# EngineeringModelBoard_6-2015_Lee_Jenny_2.net
KiCad netlist of a schematic drawn in EAGLE
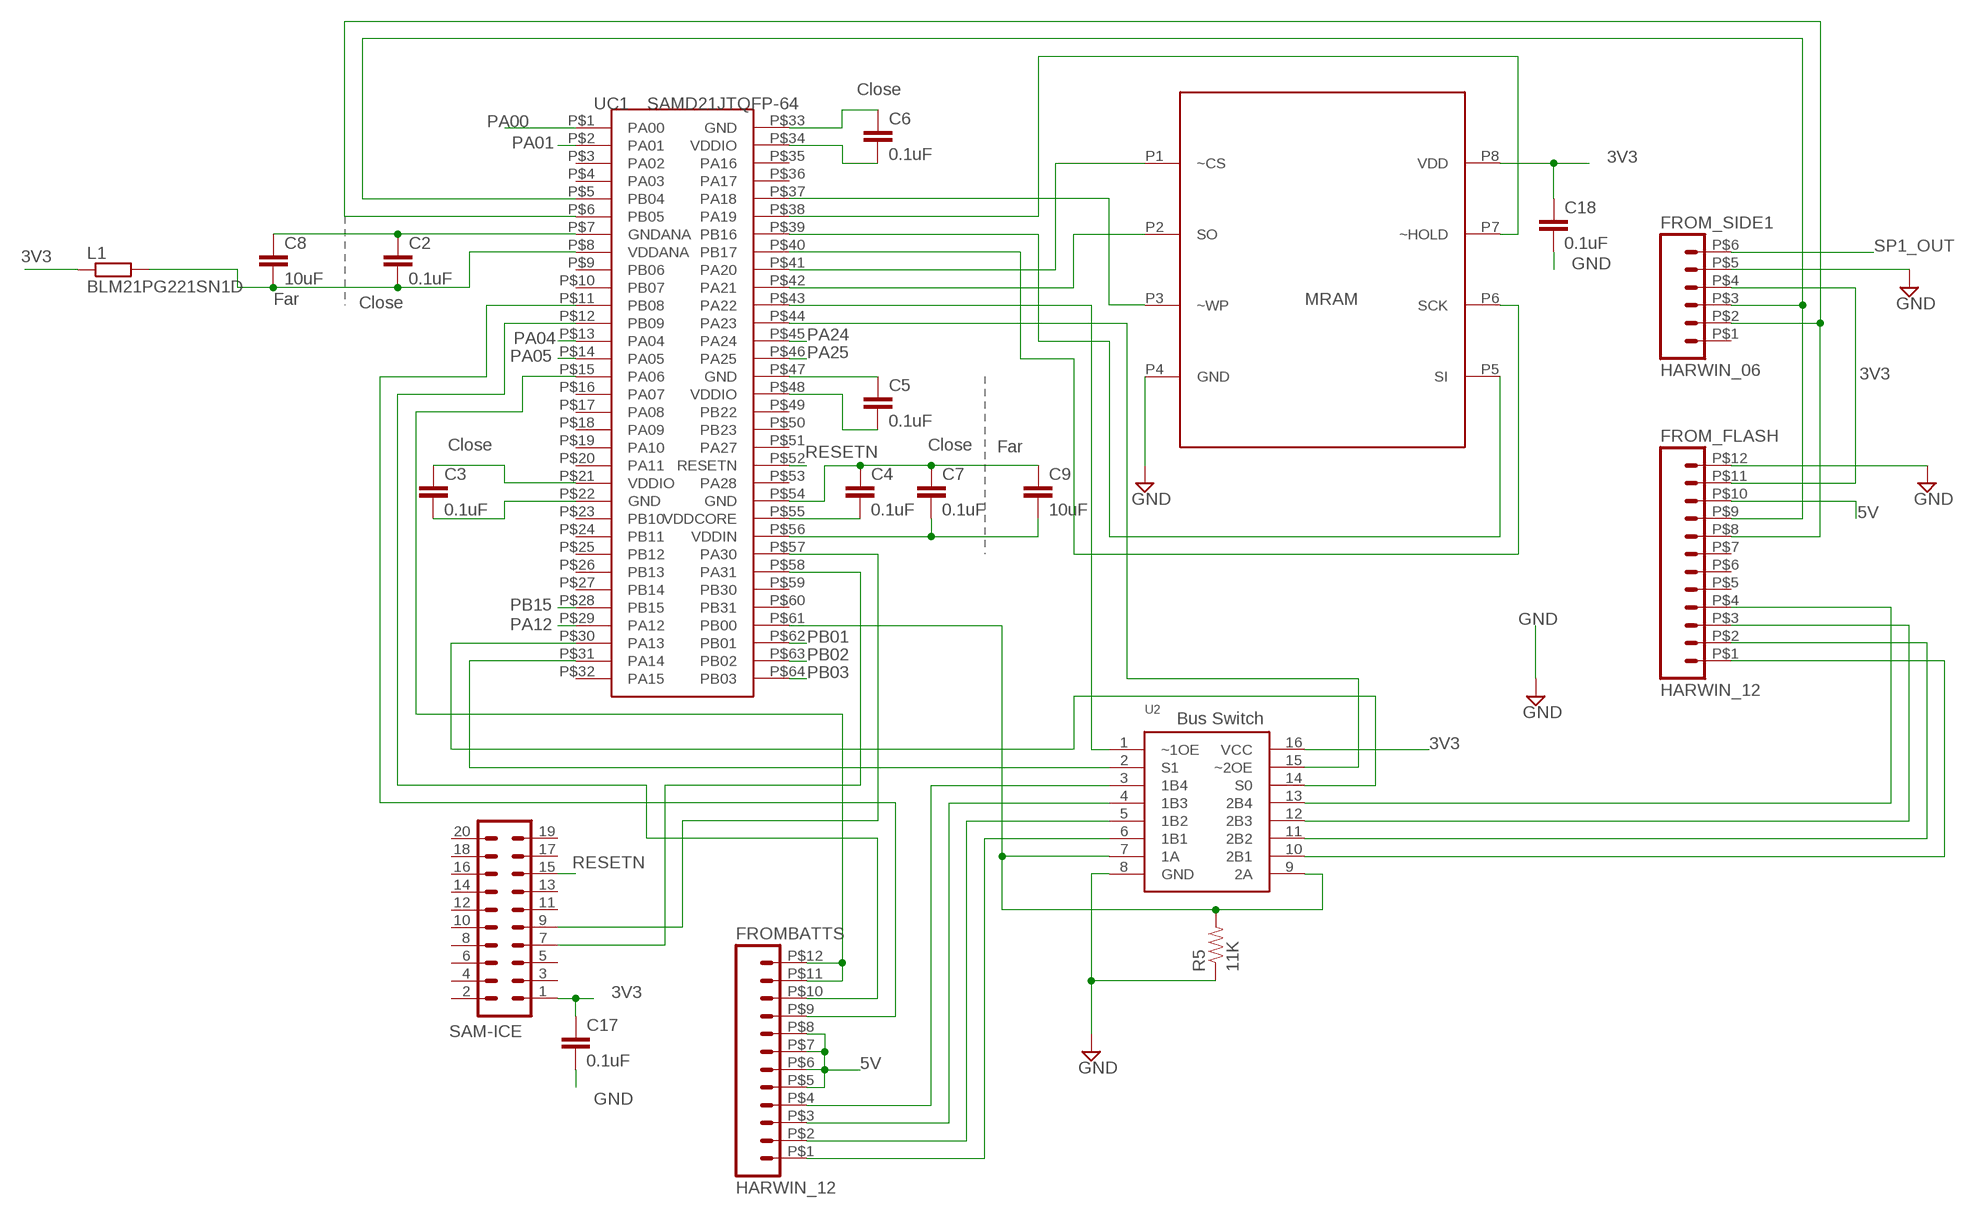
[diagram p0: schematic, sheet 1]
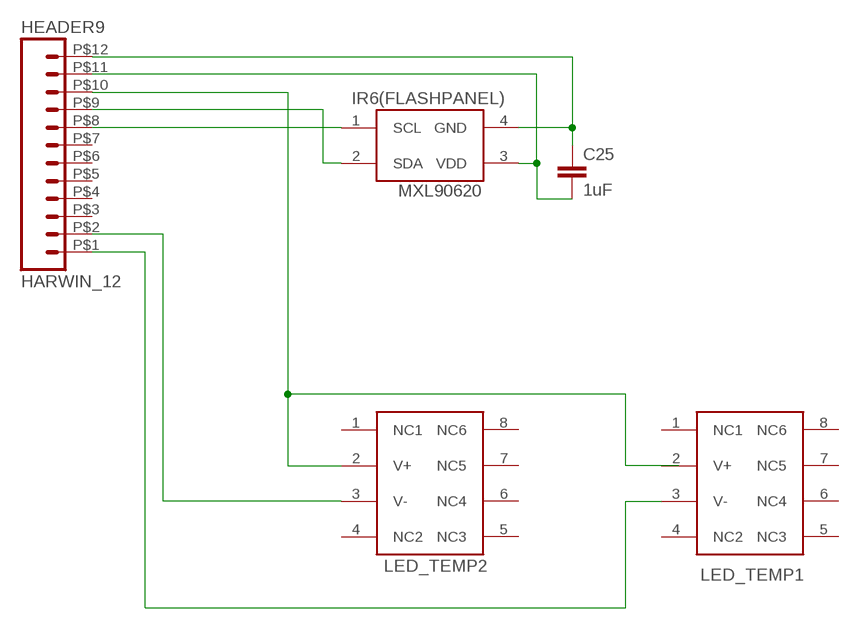
[diagram p1: schematic, sheet 2]
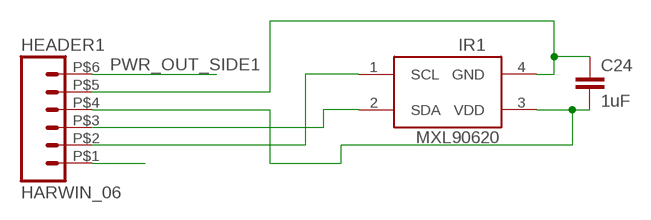
[diagram p2: schematic, sheet 3]
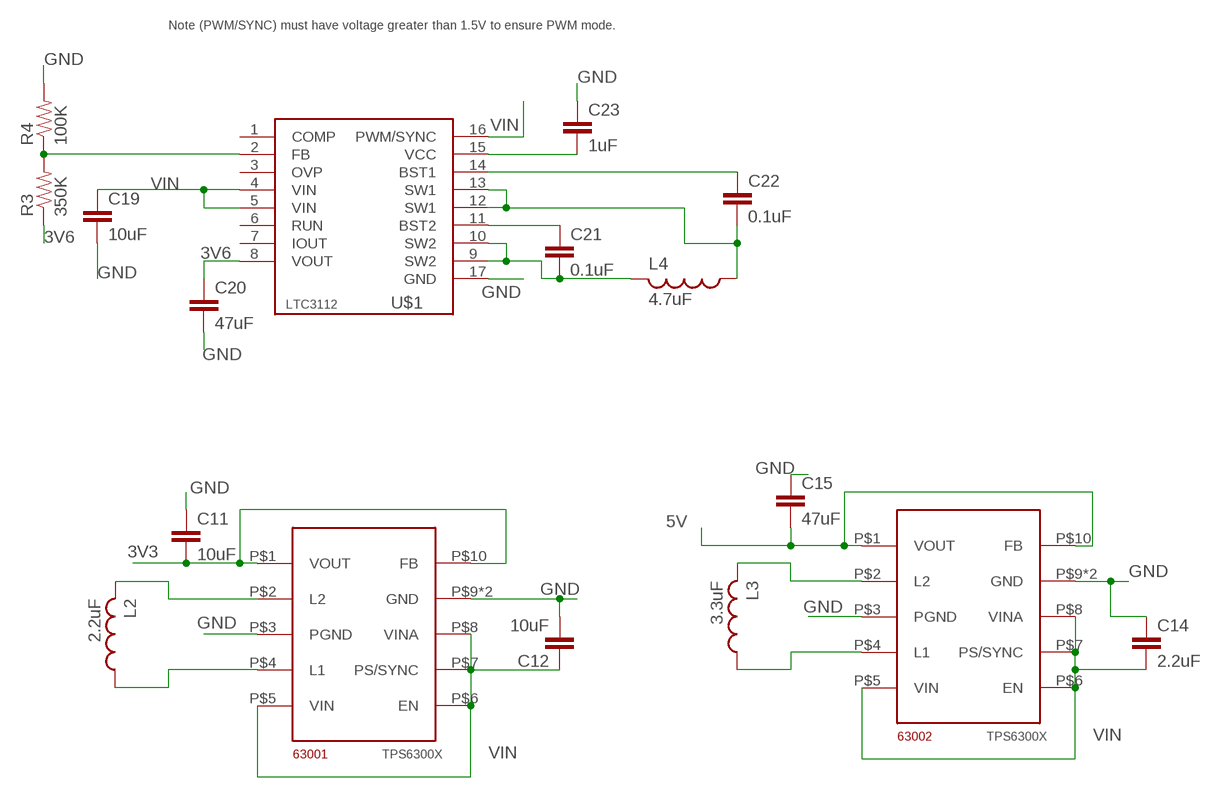
[diagram p3: schematic, sheet 4]
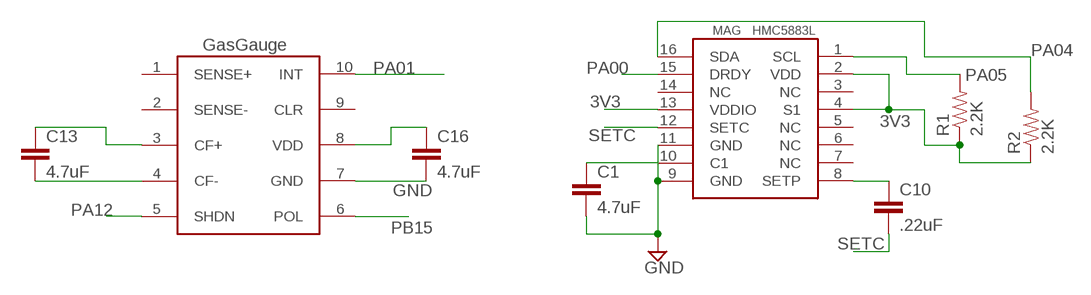
[diagram p4: schematic, sheet 5]
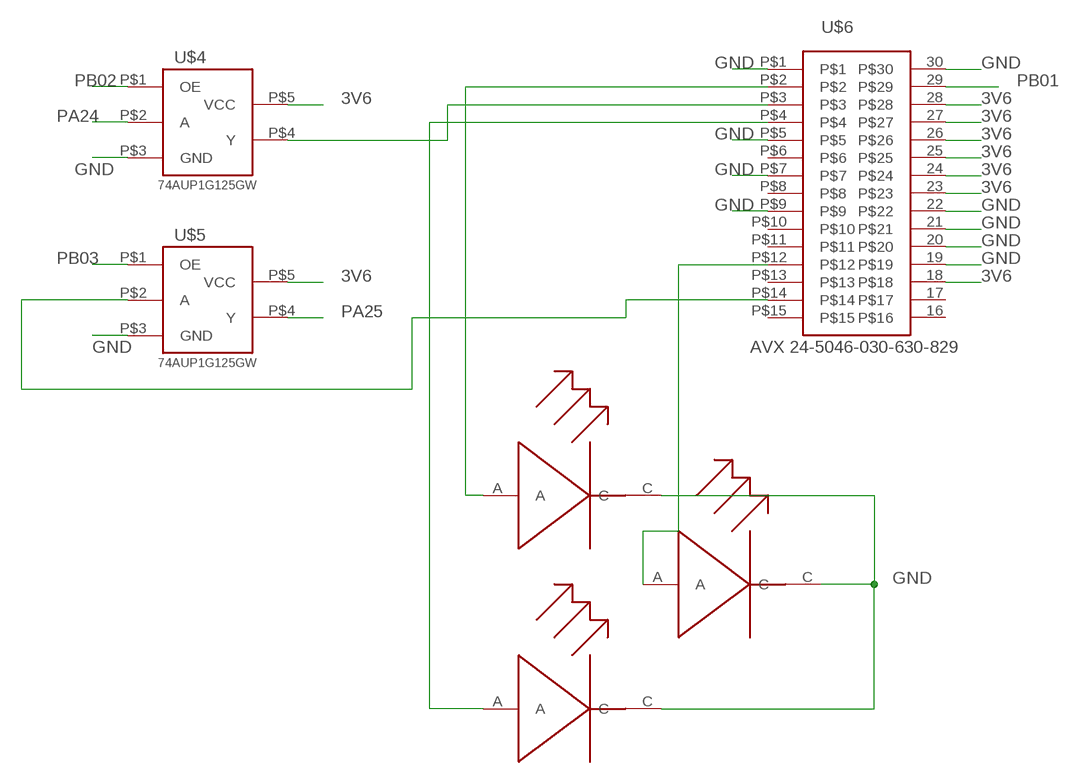
[diagram p5: schematic, sheet 6]
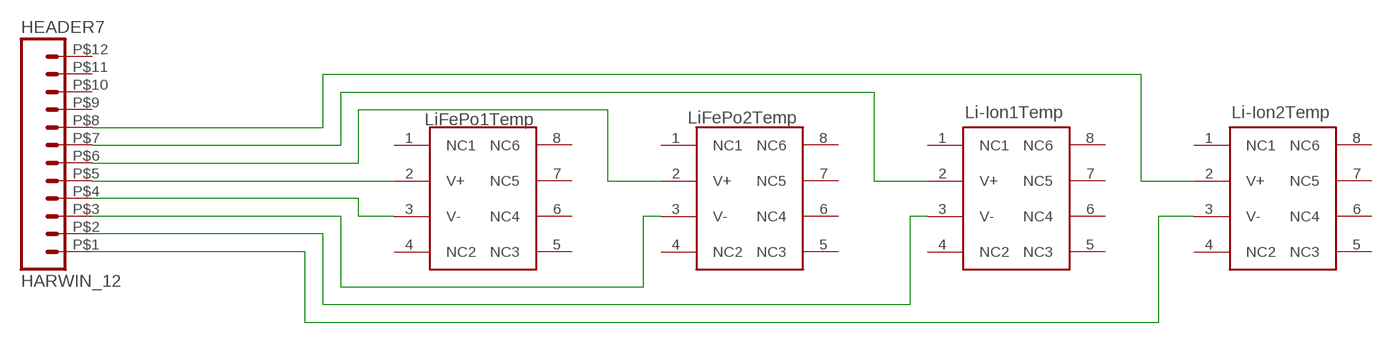
[diagram p6: schematic, sheet 7]

(export (version "E")
  (design (tool "Eeschema 10.0.6"))
  (components
    (comp (ref "C2")
      (value "0.1uF")
      (footprint "eagle-import:0805")
      (libsource (lib "eagle-import") (part "CAP0805"))
    )
    (comp (ref "C3")
      (value "0.1uF")
      (footprint "eagle-import:0805")
      (libsource (lib "eagle-import") (part "CAP0805"))
    )
    (comp (ref "C4")
      (value "0.1uF")
      (footprint "eagle-import:0805")
      (libsource (lib "eagle-import") (part "CAP0805"))
    )
    (comp (ref "C5")
      (value "0.1uF")
      (footprint "eagle-import:0805")
      (libsource (lib "eagle-import") (part "CAP0805"))
    )
    (comp (ref "C6")
      (value "0.1uF")
      (footprint "eagle-import:0805")
      (libsource (lib "eagle-import") (part "CAP0805"))
    )
    (comp (ref "C7")
      (value "0.1uF")
      (footprint "eagle-import:0805")
      (libsource (lib "eagle-import") (part "CAP0805"))
    )
    (comp (ref "C8")
      (value "10uF")
      (footprint "eagle-import:0805")
      (libsource (lib "eagle-import") (part "CAP0805"))
    )
    (comp (ref "C9")
      (value "10uF")
      (footprint "eagle-import:0805")
      (libsource (lib "eagle-import") (part "CAP0805"))
    )
    (comp (ref "C17")
      (value "0.1uF")
      (footprint "eagle-import:0805")
      (libsource (lib "eagle-import") (part "CAP0805"))
    )
    (comp (ref "C18")
      (value "0.1uF")
      (footprint "eagle-import:0805")
      (libsource (lib "eagle-import") (part "CAP0805"))
    )
    (comp (ref "FROMBATTS")
      (value "HARWIN_12")
      (footprint "eagle-import:HARWIN_DATAMATE_12")
      (libsource (lib "eagle-import") (part "HARWIN_12"))
    )
    (comp (ref "FROM_FLASH")
      (value "HARWIN_12")
      (footprint "eagle-import:HARWIN_DATAMATE_12")
      (libsource (lib "eagle-import") (part "HARWIN_12"))
    )
    (comp (ref "FROM_SIDE1")
      (value "HARWIN_06")
      (footprint "eagle-import:HARWIN_DATAMATE_6")
      (libsource (lib "eagle-import") (part "HARWIN_06"))
    )
    (comp (ref "L1")
      (value "BLM21PG221SN1D")
      (footprint "eagle-import:R0805")
      (libsource (lib "eagle-import") (part "R-EU_R0805"))
    )
    (comp (ref "R5")
      (value "11K")
      (footprint "eagle-import:0805")
      (libsource (lib "eagle-import") (part "RESISTOR"))
    )
    (comp (ref "SAM-ICE")
      (value "IDC_JTAG_CONNECTOR")
      (footprint "eagle-import:2X10")
      (libsource (lib "eagle-import") (part "IDC_JTAG_CONNECTOR"))
    )
    (comp (ref "U$3")
      (value "MRAM")
      (footprint "eagle-import:8PXMO-229")
      (libsource (lib "eagle-import") (part "MR25H10CDC"))
    )
    (comp (ref "U2")
      (value "SN74CBTLV3253")
      (footprint "eagle-import:SOIC16R")
      (libsource (lib "eagle-import") (part "SN74CBTLV3253"))
    )
    (comp (ref "UC1")
      (value "SAMD21JTQFP-64")
      (footprint "eagle-import:TQFP-64")
      (libsource (lib "eagle-import") (part "SAMD21JTQFP-64"))
    )
    (comp (ref "U$4")
      (value "74AUP1G125GW")
      (footprint "eagle-import:TSSOP-5")
      (libsource (lib "eagle-import") (part "74AUP1G125GW"))
    )
    (comp (ref "U$5")
      (value "74AUP1G125GW")
      (footprint "eagle-import:TSSOP-5")
      (libsource (lib "eagle-import") (part "74AUP1G125GW"))
    )
    (comp (ref "U$6")
      (value "AVX-24-5046-030-630-829")
      (footprint "eagle-import:AVX-24-5046-630-829")
      (libsource (lib "eagle-import") (part "AVX-24-5046-030-630-829"))
    )
    (comp (ref "U$11")
      (value "LT-T673-Q1R2-25-Z")
      (footprint "eagle-import:PLCC-2")
      (libsource (lib "eagle-import") (part "LT-T673-Q1R2-25-Z"))
    )
    (comp (ref "U$12")
      (value "LT-T673-Q1R2-25-Z")
      (footprint "eagle-import:PLCC-2")
      (libsource (lib "eagle-import") (part "LT-T673-Q1R2-25-Z"))
    )
    (comp (ref "U$13")
      (value "LT-T673-Q1R2-25-Z")
      (footprint "eagle-import:PLCC-2")
      (libsource (lib "eagle-import") (part "LT-T673-Q1R2-25-Z"))
    )
    (comp (ref "63001")
      (value "TPS6300X")
      (footprint "eagle-import:QFN10_POWERPAD")
      (libsource (lib "eagle-import") (part "TPS6300X"))
    )
    (comp (ref "63002")
      (value "TPS6300X")
      (footprint "eagle-import:QFN10_POWERPAD")
      (libsource (lib "eagle-import") (part "TPS6300X"))
    )
    (comp (ref "C11")
      (value "10uF")
      (footprint "eagle-import:0603-CAP")
      (libsource (lib "eagle-import") (part "CAP0603-CAP"))
    )
    (comp (ref "C12")
      (value "10uF")
      (footprint "eagle-import:0603-CAP")
      (libsource (lib "eagle-import") (part "CAP0603-CAP"))
    )
    (comp (ref "C14")
      (value "2.2uF")
      (footprint "eagle-import:0603-CAP")
      (libsource (lib "eagle-import") (part "CAP0603-CAP"))
    )
    (comp (ref "C15")
      (value "47uF")
      (footprint "eagle-import:0603-CAP")
      (libsource (lib "eagle-import") (part "CAP0603-CAP"))
    )
    (comp (ref "C19")
      (value "10uF")
      (footprint "eagle-import:0603-CAP")
      (libsource (lib "eagle-import") (part "CAP0603-CAP"))
    )
    (comp (ref "C20")
      (value "47uF")
      (footprint "eagle-import:0603-CAP")
      (libsource (lib "eagle-import") (part "CAP0603-CAP"))
    )
    (comp (ref "C21")
      (value "0.1uF")
      (footprint "eagle-import:0603-CAP")
      (libsource (lib "eagle-import") (part "CAP0603-CAP"))
    )
    (comp (ref "C22")
      (value "0.1uF")
      (footprint "eagle-import:0603-CAP")
      (libsource (lib "eagle-import") (part "CAP0603-CAP"))
    )
    (comp (ref "C23")
      (value "1uF")
      (footprint "eagle-import:0603-CAP")
      (libsource (lib "eagle-import") (part "CAP0603-CAP"))
    )
    (comp (ref "L2")
      (value "2.2uF")
      (footprint "eagle-import:L3225M")
      (libsource (lib "eagle-import") (part "L-USL3225M"))
    )
    (comp (ref "L3")
      (value "3.3uF")
      (footprint "eagle-import:L3225M")
      (libsource (lib "eagle-import") (part "L-USL3225M"))
    )
    (comp (ref "L4")
      (value "4.7uF")
      (footprint "eagle-import:L3225M")
      (libsource (lib "eagle-import") (part "L-USL3225M"))
    )
    (comp (ref "R3")
      (value "350K")
      (footprint "eagle-import:0805")
      (libsource (lib "eagle-import") (part "RESISTOR"))
    )
    (comp (ref "R4")
      (value "100K")
      (footprint "eagle-import:0805")
      (libsource (lib "eagle-import") (part "RESISTOR"))
    )
    (comp (ref "U$1")
      (value "LTC3112")
      (footprint "eagle-import:DHD16")
      (libsource (lib "eagle-import") (part "LTC3112"))
    )
    (comp (ref "HEADER7")
      (value "HARWIN_12")
      (footprint "eagle-import:HARWIN_DATAMATE_12")
      (libsource (lib "eagle-import") (part "HARWIN_12"))
    )
    (comp (ref "U$7")
      (value "AD590")
      (footprint "eagle-import:SO8")
      (libsource (lib "eagle-import") (part "AD590"))
    )
    (comp (ref "U$8")
      (value "AD590")
      (footprint "eagle-import:SO8")
      (libsource (lib "eagle-import") (part "AD590"))
    )
    (comp (ref "U$9")
      (value "AD590")
      (footprint "eagle-import:SO8")
      (libsource (lib "eagle-import") (part "AD590"))
    )
    (comp (ref "U$10")
      (value "AD590")
      (footprint "eagle-import:SO8")
      (libsource (lib "eagle-import") (part "AD590"))
    )
    (comp (ref "C24")
      (value "1uF")
      (footprint "eagle-import:0805")
      (libsource (lib "eagle-import") (part "CAP0805"))
    )
    (comp (ref "HEADER1")
      (value "HARWIN_06")
      (footprint "eagle-import:HARWIN_DATAMATE_6")
      (libsource (lib "eagle-import") (part "HARWIN_06"))
    )
    (comp (ref "IR1")
      (value "MXL90620")
      (footprint "eagle-import:MXL90620")
      (libsource (lib "eagle-import") (part "MXL90620"))
    )
    (comp (ref "C1")
      (value "4.7uF")
      (footprint "eagle-import:0805")
      (libsource (lib "eagle-import") (part "CAP0805"))
    )
    (comp (ref "C10")
      (value ".22uF")
      (footprint "eagle-import:0805")
      (libsource (lib "eagle-import") (part "CAP0805"))
    )
    (comp (ref "C13")
      (value "4.7uF")
      (footprint "eagle-import:0805")
      (libsource (lib "eagle-import") (part "CAP0805"))
    )
    (comp (ref "C16")
      (value "4.7uF")
      (footprint "eagle-import:0805")
      (libsource (lib "eagle-import") (part "CAP0805"))
    )
    (comp (ref "MAG")
      (value "HMC5883L")
      (footprint "eagle-import:HMC5883L")
      (libsource (lib "eagle-import") (part "HMC5883L"))
    )
    (comp (ref "R1")
      (value "2.2K")
      (footprint "eagle-import:0805")
      (libsource (lib "eagle-import") (part "RESISTOR"))
    )
    (comp (ref "R2")
      (value "2.2K")
      (footprint "eagle-import:0805")
      (libsource (lib "eagle-import") (part "RESISTOR"))
    )
    (comp (ref "U$2")
      (value "LTC4150")
      (footprint "eagle-import:MSOP10")
      (libsource (lib "eagle-import") (part "LTC4150"))
    )
    (comp (ref "C25")
      (value "1uF")
      (footprint "eagle-import:0805")
      (libsource (lib "eagle-import") (part "CAP0805"))
    )
    (comp (ref "HEADER9")
      (value "HARWIN_12")
      (footprint "eagle-import:HARWIN_DATAMATE_12")
      (libsource (lib "eagle-import") (part "HARWIN_12"))
    )
    (comp (ref "IR6(FLASHPANEL)")
      (value "MXL90620")
      (footprint "eagle-import:MXL90620")
      (libsource (lib "eagle-import") (part "MXL90620"))
    )
    (comp (ref "LED_TEMP_1")
      (value "AD590")
      (footprint "eagle-import:SO8")
      (libsource (lib "eagle-import") (part "AD590"))
    )
    (comp (ref "LED_TEMP_2")
      (value "AD590")
      (footprint "eagle-import:SO8")
      (libsource (lib "eagle-import") (part "AD590"))
    )
  )
  (nets
    (net (code "1") (name "3V3") (class "Default")
      (node (ref "63001") (pin "P$1") (pinfunction "VOUT_P$1") (pintype "output"))
      (node (ref "63001") (pin "P$10") (pinfunction "FB_P$10") (pintype "input"))
      (node (ref "C11") (pin "2") (pinfunction "2_2") (pintype "passive"))
      (node (ref "C17") (pin "1") (pinfunction "1_1") (pintype "passive"))
      (node (ref "C18") (pin "1") (pinfunction "1_1") (pintype "passive"))
      (node (ref "FROM_FLASH") (pin "P$11") (pinfunction "11_P$11") (pintype "passive"))
      (node (ref "FROM_SIDE1") (pin "P$4") (pinfunction "4_P$4") (pintype "passive"))
      (node (ref "L1") (pin "1") (pinfunction "1_1") (pintype "passive"))
      (node (ref "MAG") (pin "13") (pinfunction "VDDIO_13") (pintype "bidirectional"))
      (node (ref "MAG") (pin "2") (pinfunction "VDD_2") (pintype "bidirectional"))
      (node (ref "MAG") (pin "4") (pinfunction "S1_4") (pintype "bidirectional"))
      (node (ref "R1") (pin "1") (pinfunction "1_1") (pintype "passive"))
      (node (ref "R2") (pin "1") (pinfunction "1_1") (pintype "passive"))
      (node (ref "SAM-ICE") (pin "1") (pinfunction "1_1") (pintype "passive"))
      (node (ref "U$3") (pin "P8") (pinfunction "VDD_P8") (pintype "bidirectional"))
      (node (ref "U2") (pin "16") (pinfunction "VCC_16") (pintype "bidirectional"))
    )
    (net (code "2") (name "3V6") (class "Default")
      (node (ref "C20") (pin "1") (pinfunction "1_1") (pintype "passive"))
      (node (ref "R3") (pin "1") (pinfunction "1_1") (pintype "passive"))
      (node (ref "U$1") (pin "8") (pinfunction "VOUT_8") (pintype "bidirectional"))
      (node (ref "U$4") (pin "P$5") (pinfunction "VCC_P$5") (pintype "bidirectional"))
      (node (ref "U$5") (pin "P$5") (pinfunction "VCC_P$5") (pintype "bidirectional"))
      (node (ref "U$6") (pin "18") (pinfunction "P$18_18") (pintype "bidirectional"))
      (node (ref "U$6") (pin "23") (pinfunction "P$23_23") (pintype "bidirectional"))
      (node (ref "U$6") (pin "24") (pinfunction "P$24_24") (pintype "bidirectional"))
      (node (ref "U$6") (pin "25") (pinfunction "P$25_25") (pintype "bidirectional"))
      (node (ref "U$6") (pin "26") (pinfunction "P$26_26") (pintype "bidirectional"))
      (node (ref "U$6") (pin "27") (pinfunction "P$27_27") (pintype "bidirectional"))
      (node (ref "U$6") (pin "28") (pinfunction "P$28_28") (pintype "bidirectional"))
    )
    (net (code "3") (name "5V") (class "Default")
      (node (ref "63002") (pin "P$1") (pinfunction "VOUT_P$1") (pintype "output"))
      (node (ref "63002") (pin "P$10") (pinfunction "FB_P$10") (pintype "input"))
      (node (ref "C15") (pin "2") (pinfunction "2_2") (pintype "passive"))
      (node (ref "FROMBATTS") (pin "P$5") (pinfunction "5_P$5") (pintype "passive"))
      (node (ref "FROMBATTS") (pin "P$6") (pinfunction "6_P$6") (pintype "passive"))
      (node (ref "FROMBATTS") (pin "P$7") (pinfunction "7_P$7") (pintype "passive"))
      (node (ref "FROMBATTS") (pin "P$8") (pinfunction "8_P$8") (pintype "passive"))
      (node (ref "FROM_FLASH") (pin "P$10") (pinfunction "10_P$10") (pintype "passive"))
    )
    (net (code "4") (name "GND") (class "Default")
      (node (ref "63001") (pin "P$3") (pinfunction "PGND_P$3") (pintype "input"))
      (node (ref "63001") (pin "P$9") (pinfunction "GND_P$9") (pintype "input"))
      (node (ref "63001") (pin "PAD") (pinfunction "GND_PAD") (pintype "input"))
      (node (ref "63002") (pin "P$3") (pinfunction "PGND_P$3") (pintype "input"))
      (node (ref "63002") (pin "P$9") (pinfunction "GND_P$9") (pintype "input"))
      (node (ref "63002") (pin "PAD") (pinfunction "GND_PAD") (pintype "input"))
      (node (ref "C1") (pin "2") (pinfunction "2_2") (pintype "passive"))
      (node (ref "C11") (pin "1") (pinfunction "1_1") (pintype "passive"))
      (node (ref "C12") (pin "2") (pinfunction "2_2") (pintype "passive"))
      (node (ref "C14") (pin "1") (pinfunction "1_1") (pintype "passive"))
      (node (ref "C15") (pin "1") (pinfunction "1_1") (pintype "passive"))
      (node (ref "C16") (pin "2") (pinfunction "2_2") (pintype "passive"))
      (node (ref "C17") (pin "2") (pinfunction "2_2") (pintype "passive"))
      (node (ref "C18") (pin "2") (pinfunction "2_2") (pintype "passive"))
      (node (ref "C19") (pin "2") (pinfunction "2_2") (pintype "passive"))
      (node (ref "C2") (pin "1") (pinfunction "1_1") (pintype "passive"))
      (node (ref "C20") (pin "2") (pinfunction "2_2") (pintype "passive"))
      (node (ref "C23") (pin "1") (pinfunction "1_1") (pintype "passive"))
      (node (ref "C4") (pin "1") (pinfunction "1_1") (pintype "passive"))
      (node (ref "C5") (pin "1") (pinfunction "1_1") (pintype "passive"))
      (node (ref "C6") (pin "1") (pinfunction "1_1") (pintype "passive"))
      (node (ref "C7") (pin "1") (pinfunction "1_1") (pintype "passive"))
      (node (ref "C8") (pin "1") (pinfunction "1_1") (pintype "passive"))
      (node (ref "C9") (pin "1") (pinfunction "1_1") (pintype "passive"))
      (node (ref "FROM_FLASH") (pin "P$12") (pinfunction "12_P$12") (pintype "passive"))
      (node (ref "FROM_SIDE1") (pin "P$5") (pinfunction "5_P$5") (pintype "passive"))
      (node (ref "MAG") (pin "11") (pinfunction "GND_11") (pintype "bidirectional"))
      (node (ref "MAG") (pin "9") (pinfunction "GND_9") (pintype "bidirectional"))
      (node (ref "R4") (pin "2") (pinfunction "2_2") (pintype "passive"))
      (node (ref "R5") (pin "1") (pinfunction "1_1") (pintype "passive"))
      (node (ref "U$1") (pin "17") (pinfunction "GND_17") (pintype "bidirectional"))
      (node (ref "U$11") (pin "C") (pinfunction "C_C") (pintype "bidirectional"))
      (node (ref "U$12") (pin "C") (pinfunction "C_C") (pintype "bidirectional"))
      (node (ref "U$13") (pin "C") (pinfunction "C_C") (pintype "bidirectional"))
      (node (ref "U$2") (pin "7") (pinfunction "GND_7") (pintype "bidirectional"))
      (node (ref "U$3") (pin "P4") (pinfunction "GND_P4") (pintype "bidirectional"))
      (node (ref "U$4") (pin "P$3") (pinfunction "GND_P$3") (pintype "bidirectional"))
      (node (ref "U$5") (pin "P$3") (pinfunction "GND_P$3") (pintype "bidirectional"))
      (node (ref "U$6") (pin "19") (pinfunction "P$19_19") (pintype "bidirectional"))
      (node (ref "U$6") (pin "20") (pinfunction "P$20_20") (pintype "bidirectional"))
      (node (ref "U$6") (pin "21") (pinfunction "P$21_21") (pintype "bidirectional"))
      (node (ref "U$6") (pin "22") (pinfunction "P$22_22") (pintype "bidirectional"))
      (node (ref "U$6") (pin "30") (pinfunction "P$30_30") (pintype "bidirectional"))
      (node (ref "U$6") (pin "P$1") (pinfunction "P$1_P$1") (pintype "bidirectional"))
      (node (ref "U$6") (pin "P$5") (pinfunction "P$5_P$5") (pintype "bidirectional"))
      (node (ref "U$6") (pin "P$7") (pinfunction "P$7_P$7") (pintype "bidirectional"))
      (node (ref "U$6") (pin "P$9") (pinfunction "P$9_P$9") (pintype "bidirectional"))
      (node (ref "U2") (pin "8") (pinfunction "GND_8") (pintype "bidirectional"))
      (node (ref "UC1") (pin "P$33") (pinfunction "GND_P$33") (pintype "power_in"))
      (node (ref "UC1") (pin "P$47") (pinfunction "GND_P$47") (pintype "power_in"))
      (node (ref "UC1") (pin "P$54") (pinfunction "GND_P$54") (pintype "power_in"))
      (node (ref "UC1") (pin "P$7") (pinfunction "GNDANA_P$7") (pintype "power_in"))
    )
    (net (code "5") (name "Net-(63001-L1)") (class "Default")
      (node (ref "63001") (pin "P$4") (pinfunction "L1_P$4") (pintype "input"))
      (node (ref "L2") (pin "1") (pinfunction "1_1") (pintype "passive"))
    )
    (net (code "6") (name "Net-(63001-L2)") (class "Default")
      (node (ref "63001") (pin "P$2") (pinfunction "L2_P$2") (pintype "input"))
      (node (ref "L2") (pin "2") (pinfunction "2_2") (pintype "passive"))
    )
    (net (code "7") (name "Net-(63002-L1)") (class "Default")
      (node (ref "63002") (pin "P$4") (pinfunction "L1_P$4") (pintype "input"))
      (node (ref "L3") (pin "1") (pinfunction "1_1") (pintype "passive"))
    )
    (net (code "8") (name "Net-(63002-L2)") (class "Default")
      (node (ref "63002") (pin "P$2") (pinfunction "L2_P$2") (pintype "input"))
      (node (ref "L3") (pin "2") (pinfunction "2_2") (pintype "passive"))
    )
    (net (code "9") (name "Net-(C3-Pad1)") (class "Default")
      (node (ref "C3") (pin "1") (pinfunction "1_1") (pintype "passive"))
      (node (ref "UC1") (pin "P$21") (pinfunction "VDDIO_P$21") (pintype "power_in"))
    )
    (net (code "10") (name "Net-(C3-Pad2)") (class "Default")
      (node (ref "C3") (pin "2") (pinfunction "2_2") (pintype "passive"))
      (node (ref "UC1") (pin "P$22") (pinfunction "GND_P$22") (pintype "power_in"))
    )
    (net (code "11") (name "Net-(C5-Pad2)") (class "Default")
      (node (ref "C5") (pin "2") (pinfunction "2_2") (pintype "passive"))
      (node (ref "UC1") (pin "P$48") (pinfunction "VDDIO_P$48") (pintype "power_in"))
    )
    (net (code "12") (name "Net-(C6-Pad2)") (class "Default")
      (node (ref "C6") (pin "2") (pinfunction "2_2") (pintype "passive"))
      (node (ref "UC1") (pin "P$34") (pinfunction "VDDIO_P$34") (pintype "power_in"))
    )
    (net (code "13") (name "Net-(C21-Pad2)") (class "Default")
      (node (ref "C21") (pin "2") (pinfunction "2_2") (pintype "passive"))
      (node (ref "L4") (pin "2") (pinfunction "2_2") (pintype "passive"))
      (node (ref "U$1") (pin "10") (pinfunction "SW2_10") (pintype "bidirectional"))
      (node (ref "U$1") (pin "9") (pinfunction "SW2_9") (pintype "bidirectional"))
    )
    (net (code "14") (name "Net-(C22-Pad2)") (class "Default")
      (node (ref "C22") (pin "2") (pinfunction "2_2") (pintype "passive"))
      (node (ref "L4") (pin "1") (pinfunction "1_1") (pintype "passive"))
      (node (ref "U$1") (pin "12") (pinfunction "SW1_12") (pintype "bidirectional"))
      (node (ref "U$1") (pin "13") (pinfunction "SW1_13") (pintype "bidirectional"))
    )
    (net (code "15") (name "Net-(FROMBATTS-1)") (class "Default")
      (node (ref "FROMBATTS") (pin "P$1") (pinfunction "1_P$1") (pintype "passive"))
      (node (ref "U2") (pin "6") (pinfunction "1B1_6") (pintype "bidirectional"))
    )
    (net (code "16") (name "Net-(FROMBATTS-2)") (class "Default")
      (node (ref "FROMBATTS") (pin "P$2") (pinfunction "2_P$2") (pintype "passive"))
      (node (ref "U2") (pin "5") (pinfunction "1B2_5") (pintype "bidirectional"))
    )
    (net (code "17") (name "Net-(FROMBATTS-3)") (class "Default")
      (node (ref "FROMBATTS") (pin "P$3") (pinfunction "3_P$3") (pintype "passive"))
      (node (ref "U2") (pin "4") (pinfunction "1B3_4") (pintype "bidirectional"))
    )
    (net (code "18") (name "Net-(FROMBATTS-4)") (class "Default")
      (node (ref "FROMBATTS") (pin "P$4") (pinfunction "4_P$4") (pintype "passive"))
      (node (ref "U2") (pin "3") (pinfunction "1B4_3") (pintype "bidirectional"))
    )
    (net (code "19") (name "Net-(FROMBATTS-9)") (class "Default")
      (node (ref "FROMBATTS") (pin "P$9") (pinfunction "9_P$9") (pintype "passive"))
      (node (ref "UC1") (pin "P$11") (pinfunction "PB08_P$11") (pintype "bidirectional"))
    )
    (net (code "20") (name "Net-(FROMBATTS-10)") (class "Default")
      (node (ref "FROMBATTS") (pin "P$10") (pinfunction "10_P$10") (pintype "passive"))
      (node (ref "UC1") (pin "P$12") (pinfunction "PB09_P$12") (pintype "bidirectional"))
    )
    (net (code "21") (name "Net-(FROMBATTS-11)") (class "Default")
      (node (ref "FROMBATTS") (pin "P$11") (pinfunction "11_P$11") (pintype "passive"))
      (node (ref "FROMBATTS") (pin "P$12") (pinfunction "12_P$12") (pintype "passive"))
      (node (ref "UC1") (pin "P$15") (pinfunction "PA06_P$15") (pintype "bidirectional"))
    )
    (net (code "22") (name "Net-(FROM_FLASH-1)") (class "Default")
      (node (ref "FROM_FLASH") (pin "P$1") (pinfunction "1_P$1") (pintype "passive"))
      (node (ref "U2") (pin "10") (pinfunction "2B1_10") (pintype "bidirectional"))
    )
    (net (code "23") (name "Net-(FROM_FLASH-2)") (class "Default")
      (node (ref "FROM_FLASH") (pin "P$2") (pinfunction "2_P$2") (pintype "passive"))
      (node (ref "U2") (pin "11") (pinfunction "2B2_11") (pintype "bidirectional"))
    )
    (net (code "24") (name "Net-(FROM_FLASH-3)") (class "Default")
      (node (ref "FROM_FLASH") (pin "P$3") (pinfunction "3_P$3") (pintype "passive"))
      (node (ref "U2") (pin "12") (pinfunction "2B3_12") (pintype "bidirectional"))
    )
    (net (code "25") (name "Net-(FROM_FLASH-4)") (class "Default")
      (node (ref "FROM_FLASH") (pin "P$4") (pinfunction "4_P$4") (pintype "passive"))
      (node (ref "U2") (pin "13") (pinfunction "2B4_13") (pintype "bidirectional"))
    )
    (net (code "26") (name "Net-(FROM_FLASH-8)") (class "Default")
      (node (ref "FROM_FLASH") (pin "P$8") (pinfunction "8_P$8") (pintype "passive"))
      (node (ref "FROM_SIDE1") (pin "P$2") (pinfunction "2_P$2") (pintype "passive"))
      (node (ref "UC1") (pin "P$6") (pinfunction "PB05_P$6") (pintype "bidirectional"))
    )
    (net (code "27") (name "Net-(FROM_FLASH-9)") (class "Default")
      (node (ref "FROM_FLASH") (pin "P$9") (pinfunction "9_P$9") (pintype "passive"))
      (node (ref "FROM_SIDE1") (pin "P$3") (pinfunction "3_P$3") (pintype "passive"))
      (node (ref "UC1") (pin "P$5") (pinfunction "PB04_P$5") (pintype "bidirectional"))
    )
    (net (code "28") (name "Net-(HEADER1-2)") (class "Default")
      (node (ref "HEADER1") (pin "P$2") (pinfunction "2_P$2") (pintype "passive"))
      (node (ref "IR1") (pin "1") (pinfunction "SCL_1") (pintype "bidirectional"))
    )
    (net (code "29") (name "Net-(HEADER1-3)") (class "Default")
      (node (ref "HEADER1") (pin "P$3") (pinfunction "3_P$3") (pintype "passive"))
      (node (ref "IR1") (pin "2") (pinfunction "SDA_2") (pintype "bidirectional"))
    )
    (net (code "30") (name "Net-(HEADER1-4)") (class "Default")
      (node (ref "C24") (pin "2") (pinfunction "2_2") (pintype "passive"))
      (node (ref "HEADER1") (pin "P$4") (pinfunction "4_P$4") (pintype "passive"))
      (node (ref "IR1") (pin "3") (pinfunction "VDD_3") (pintype "bidirectional"))
    )
    (net (code "31") (name "Net-(HEADER1-5)") (class "Default")
      (node (ref "C24") (pin "1") (pinfunction "1_1") (pintype "passive"))
      (node (ref "HEADER1") (pin "P$5") (pinfunction "5_P$5") (pintype "passive"))
      (node (ref "IR1") (pin "4") (pinfunction "GND_4") (pintype "bidirectional"))
    )
    (net (code "32") (name "Net-(HEADER7-1)") (class "Default")
      (node (ref "HEADER7") (pin "P$1") (pinfunction "1_P$1") (pintype "passive"))
      (node (ref "U$10") (pin "3") (pinfunction "V-_3") (pintype "bidirectional"))
    )
    (net (code "33") (name "Net-(HEADER7-2)") (class "Default")
      (node (ref "HEADER7") (pin "P$2") (pinfunction "2_P$2") (pintype "passive"))
      (node (ref "U$9") (pin "3") (pinfunction "V-_3") (pintype "bidirectional"))
    )
    (net (code "34") (name "Net-(HEADER7-3)") (class "Default")
      (node (ref "HEADER7") (pin "P$3") (pinfunction "3_P$3") (pintype "passive"))
      (node (ref "U$8") (pin "3") (pinfunction "V-_3") (pintype "bidirectional"))
    )
    (net (code "35") (name "Net-(HEADER7-4)") (class "Default")
      (node (ref "HEADER7") (pin "P$4") (pinfunction "4_P$4") (pintype "passive"))
      (node (ref "U$7") (pin "3") (pinfunction "V-_3") (pintype "bidirectional"))
    )
    (net (code "36") (name "Net-(HEADER7-5)") (class "Default")
      (node (ref "HEADER7") (pin "P$5") (pinfunction "5_P$5") (pintype "passive"))
      (node (ref "U$7") (pin "2") (pinfunction "V+_2") (pintype "bidirectional"))
    )
    (net (code "37") (name "Net-(HEADER7-6)") (class "Default")
      (node (ref "HEADER7") (pin "P$6") (pinfunction "6_P$6") (pintype "passive"))
      (node (ref "U$8") (pin "2") (pinfunction "V+_2") (pintype "bidirectional"))
    )
    (net (code "38") (name "Net-(HEADER7-7)") (class "Default")
      (node (ref "HEADER7") (pin "P$7") (pinfunction "7_P$7") (pintype "passive"))
      (node (ref "U$9") (pin "2") (pinfunction "V+_2") (pintype "bidirectional"))
    )
    (net (code "39") (name "Net-(HEADER7-8)") (class "Default")
      (node (ref "HEADER7") (pin "P$8") (pinfunction "8_P$8") (pintype "passive"))
      (node (ref "U$10") (pin "2") (pinfunction "V+_2") (pintype "bidirectional"))
    )
    (net (code "40") (name "Net-(HEADER9-1)") (class "Default")
      (node (ref "HEADER9") (pin "P$1") (pinfunction "1_P$1") (pintype "passive"))
      (node (ref "LED_TEMP_1") (pin "3") (pinfunction "V-_3") (pintype "bidirectional"))
    )
    (net (code "41") (name "Net-(HEADER9-2)") (class "Default")
      (node (ref "HEADER9") (pin "P$2") (pinfunction "2_P$2") (pintype "passive"))
      (node (ref "LED_TEMP_2") (pin "3") (pinfunction "V-_3") (pintype "bidirectional"))
    )
    (net (code "42") (name "Net-(HEADER9-8)") (class "Default")
      (node (ref "HEADER9") (pin "P$8") (pinfunction "8_P$8") (pintype "passive"))
      (node (ref "IR6(FLASHPANEL)") (pin "1") (pinfunction "SCL_1") (pintype "bidirectional"))
    )
    (net (code "43") (name "Net-(HEADER9-9)") (class "Default")
      (node (ref "HEADER9") (pin "P$9") (pinfunction "9_P$9") (pintype "passive"))
      (node (ref "IR6(FLASHPANEL)") (pin "2") (pinfunction "SDA_2") (pintype "bidirectional"))
    )
    (net (code "44") (name "Net-(HEADER9-10)") (class "Default")
      (node (ref "HEADER9") (pin "P$10") (pinfunction "10_P$10") (pintype "passive"))
      (node (ref "LED_TEMP_2") (pin "2") (pinfunction "V+_2") (pintype "bidirectional"))
    )
    (net (code "45") (name "Net-(HEADER9-11)") (class "Default")
      (node (ref "C25") (pin "2") (pinfunction "2_2") (pintype "passive"))
      (node (ref "HEADER9") (pin "P$11") (pinfunction "11_P$11") (pintype "passive"))
      (node (ref "IR6(FLASHPANEL)") (pin "3") (pinfunction "VDD_3") (pintype "bidirectional"))
    )
    (net (code "46") (name "Net-(HEADER9-12)") (class "Default")
      (node (ref "C25") (pin "1") (pinfunction "1_1") (pintype "passive"))
      (node (ref "HEADER9") (pin "P$12") (pinfunction "12_P$12") (pintype "passive"))
      (node (ref "IR6(FLASHPANEL)") (pin "4") (pinfunction "GND_4") (pintype "bidirectional"))
    )
    (net (code "47") (name "Net-(MAG-C1)") (class "Default")
      (node (ref "C1") (pin "1") (pinfunction "1_1") (pintype "passive"))
      (node (ref "MAG") (pin "10") (pinfunction "C1_10") (pintype "bidirectional"))
    )
    (net (code "48") (name "Net-(MAG-SETP)") (class "Default")
      (node (ref "C10") (pin "1") (pinfunction "1_1") (pintype "passive"))
      (node (ref "MAG") (pin "8") (pinfunction "SETP_8") (pintype "bidirectional"))
    )
    (net (code "49") (name "Net-(U$1-BST1)") (class "Default")
      (node (ref "C22") (pin "1") (pinfunction "1_1") (pintype "passive"))
      (node (ref "U$1") (pin "14") (pinfunction "BST1_14") (pintype "bidirectional"))
    )
    (net (code "50") (name "Net-(U$1-BST2)") (class "Default")
      (node (ref "C21") (pin "1") (pinfunction "1_1") (pintype "passive"))
      (node (ref "U$1") (pin "11") (pinfunction "BST2_11") (pintype "bidirectional"))
    )
    (net (code "51") (name "Net-(U$1-FB)") (class "Default")
      (node (ref "R3") (pin "2") (pinfunction "2_2") (pintype "passive"))
      (node (ref "R4") (pin "1") (pinfunction "1_1") (pintype "passive"))
      (node (ref "U$1") (pin "2") (pinfunction "FB_2") (pintype "bidirectional"))
    )
    (net (code "52") (name "Net-(U$1-VCC)") (class "Default")
      (node (ref "C23") (pin "2") (pinfunction "2_2") (pintype "passive"))
      (node (ref "U$1") (pin "15") (pinfunction "VCC_15") (pintype "bidirectional"))
    )
    (net (code "53") (name "Net-(U$2-CF+)") (class "Default")
      (node (ref "C13") (pin "1") (pinfunction "1_1") (pintype "passive"))
      (node (ref "U$2") (pin "3") (pinfunction "CF+_3") (pintype "bidirectional"))
    )
    (net (code "54") (name "Net-(U$2-CF-)") (class "Default")
      (node (ref "C13") (pin "2") (pinfunction "2_2") (pintype "passive"))
      (node (ref "U$2") (pin "4") (pinfunction "CF-_4") (pintype "bidirectional"))
    )
    (net (code "55") (name "Net-(U$2-VDD)") (class "Default")
      (node (ref "C16") (pin "1") (pinfunction "1_1") (pintype "passive"))
      (node (ref "U$2") (pin "8") (pinfunction "VDD_8") (pintype "bidirectional"))
    )
    (net (code "56") (name "Net-(U$3-SCK)") (class "Default")
      (node (ref "U$3") (pin "P6") (pinfunction "SCK_P6") (pintype "bidirectional"))
      (node (ref "UC1") (pin "P$40") (pinfunction "PB17_P$40") (pintype "bidirectional"))
    )
    (net (code "57") (name "Net-(U$3-SI)") (class "Default")
      (node (ref "U$3") (pin "P5") (pinfunction "SI_P5") (pintype "bidirectional"))
      (node (ref "UC1") (pin "P$39") (pinfunction "PB16_P$39") (pintype "bidirectional"))
    )
    (net (code "58") (name "Net-(U$3-SO)") (class "Default")
      (node (ref "U$3") (pin "P2") (pinfunction "SO_P2") (pintype "bidirectional"))
      (node (ref "UC1") (pin "P$42") (pinfunction "PA21_P$42") (pintype "bidirectional"))
    )
    (net (code "59") (name "Net-(U$3-~{CS})") (class "Default")
      (node (ref "U$3") (pin "P1") (pinfunction "~{CS}_P1") (pintype "bidirectional"))
      (node (ref "UC1") (pin "P$41") (pinfunction "PA20_P$41") (pintype "bidirectional"))
    )
    (net (code "60") (name "Net-(U$3-~{HOLD})") (class "Default")
      (node (ref "U$3") (pin "P7") (pinfunction "~{HOLD}_P7") (pintype "bidirectional"))
      (node (ref "UC1") (pin "P$38") (pinfunction "PA19_P$38") (pintype "bidirectional"))
    )
    (net (code "61") (name "Net-(U$3-~{WP})") (class "Default")
      (node (ref "U$3") (pin "P3") (pinfunction "~{WP}_P3") (pintype "bidirectional"))
      (node (ref "UC1") (pin "P$37") (pinfunction "PA18_P$37") (pintype "bidirectional"))
    )
    (net (code "62") (name "Net-(U$4-Y)") (class "Default")
      (node (ref "U$4") (pin "P$4") (pinfunction "Y_P$4") (pintype "bidirectional"))
      (node (ref "U$6") (pin "P$3") (pinfunction "P$3_P$3") (pintype "bidirectional"))
    )
    (net (code "63") (name "Net-(U$5-A)") (class "Default")
      (node (ref "U$5") (pin "P$2") (pinfunction "A_P$2") (pintype "bidirectional"))
      (node (ref "U$6") (pin "P$14") (pinfunction "P$14_P$14") (pintype "bidirectional"))
    )
    (net (code "64") (name "Net-(U$11-PadA)") (class "Default")
      (node (ref "U$11") (pin "A") (pinfunction "A_A") (pintype "bidirectional"))
      (node (ref "U$6") (pin "P$12") (pinfunction "P$12_P$12") (pintype "bidirectional"))
    )
    (net (code "65") (name "Net-(U$12-PadA)") (class "Default")
      (node (ref "U$12") (pin "A") (pinfunction "A_A") (pintype "bidirectional"))
      (node (ref "U$6") (pin "P$4") (pinfunction "P$4_P$4") (pintype "bidirectional"))
    )
    (net (code "66") (name "Net-(U$13-PadA)") (class "Default")
      (node (ref "U$13") (pin "A") (pinfunction "A_A") (pintype "bidirectional"))
      (node (ref "U$6") (pin "P$2") (pinfunction "P$2_P$2") (pintype "bidirectional"))
    )
    (net (code "67") (name "Net-(U2-1A)") (class "Default")
      (node (ref "R5") (pin "2") (pinfunction "2_2") (pintype "passive"))
      (node (ref "U2") (pin "7") (pinfunction "1A_7") (pintype "bidirectional"))
      (node (ref "U2") (pin "9") (pinfunction "2A_9") (pintype "bidirectional"))
      (node (ref "UC1") (pin "P$61") (pinfunction "PB00_P$61") (pintype "bidirectional"))
    )
    (net (code "68") (name "Net-(U2-S0)") (class "Default")
      (node (ref "U2") (pin "14") (pinfunction "S0_14") (pintype "bidirectional"))
      (node (ref "UC1") (pin "P$30") (pinfunction "PA13_P$30") (pintype "bidirectional"))
    )
    (net (code "69") (name "Net-(U2-S1)") (class "Default")
      (node (ref "U2") (pin "2") (pinfunction "S1_2") (pintype "bidirectional"))
      (node (ref "UC1") (pin "P$31") (pinfunction "PA14_P$31") (pintype "bidirectional"))
    )
    (net (code "70") (name "Net-(U2-~{1OE})") (class "Default")
      (node (ref "U2") (pin "1") (pinfunction "~{1OE}_1") (pintype "bidirectional"))
      (node (ref "UC1") (pin "P$43") (pinfunction "PA22_P$43") (pintype "bidirectional"))
    )
    (net (code "71") (name "Net-(U2-~{2OE})") (class "Default")
      (node (ref "U2") (pin "15") (pinfunction "~{2OE}_15") (pintype "bidirectional"))
      (node (ref "UC1") (pin "P$44") (pinfunction "PA23_P$44") (pintype "bidirectional"))
    )
    (net (code "72") (name "Net-(UC1-PA30)") (class "Default")
      (node (ref "SAM-ICE") (pin "9") (pinfunction "9_9") (pintype "passive"))
      (node (ref "UC1") (pin "P$57") (pinfunction "PA30_P$57") (pintype "bidirectional"))
    )
    (net (code "73") (name "Net-(UC1-PA31)") (class "Default")
      (node (ref "SAM-ICE") (pin "7") (pinfunction "7_7") (pintype "passive"))
      (node (ref "UC1") (pin "P$58") (pinfunction "PA31_P$58") (pintype "bidirectional"))
    )
    (net (code "74") (name "Net-(UC1-VDDANA)") (class "Default")
      (node (ref "C2") (pin "2") (pinfunction "2_2") (pintype "passive"))
      (node (ref "C8") (pin "2") (pinfunction "2_2") (pintype "passive"))
      (node (ref "L1") (pin "2") (pinfunction "2_2") (pintype "passive"))
      (node (ref "UC1") (pin "P$8") (pinfunction "VDDANA_P$8") (pintype "power_in"))
    )
    (net (code "75") (name "Net-(UC1-VDDCORE)") (class "Default")
      (node (ref "C4") (pin "2") (pinfunction "2_2") (pintype "passive"))
      (node (ref "UC1") (pin "P$55") (pinfunction "VDDCORE_P$55") (pintype "power_in"))
    )
    (net (code "76") (name "Net-(UC1-VDDIN)") (class "Default")
      (node (ref "C7") (pin "2") (pinfunction "2_2") (pintype "passive"))
      (node (ref "C9") (pin "2") (pinfunction "2_2") (pintype "passive"))
      (node (ref "UC1") (pin "P$56") (pinfunction "VDDIN_P$56") (pintype "power_in"))
    )
    (net (code "77") (name "PA00") (class "Default")
      (node (ref "MAG") (pin "15") (pinfunction "DRDY_15") (pintype "bidirectional"))
      (node (ref "UC1") (pin "P$1") (pinfunction "PA00_P$1") (pintype "bidirectional"))
    )
    (net (code "78") (name "PA01") (class "Default")
      (node (ref "U$2") (pin "10") (pinfunction "INT_10") (pintype "bidirectional"))
      (node (ref "UC1") (pin "P$2") (pinfunction "PA01_P$2") (pintype "bidirectional"))
    )
    (net (code "79") (name "PA04") (class "Default")
      (node (ref "MAG") (pin "16") (pinfunction "SDA_16") (pintype "bidirectional"))
      (node (ref "R2") (pin "2") (pinfunction "2_2") (pintype "passive"))
      (node (ref "UC1") (pin "P$13") (pinfunction "PA04_P$13") (pintype "bidirectional"))
    )
    (net (code "80") (name "PA05") (class "Default")
      (node (ref "MAG") (pin "1") (pinfunction "SCL_1") (pintype "bidirectional"))
      (node (ref "R1") (pin "2") (pinfunction "2_2") (pintype "passive"))
      (node (ref "UC1") (pin "P$14") (pinfunction "PA05_P$14") (pintype "bidirectional"))
    )
    (net (code "81") (name "PA12") (class "Default")
      (node (ref "U$2") (pin "5") (pinfunction "SHDN_5") (pintype "bidirectional"))
      (node (ref "UC1") (pin "P$29") (pinfunction "PA12_P$29") (pintype "bidirectional"))
    )
    (net (code "82") (name "PA24") (class "Default")
      (node (ref "U$4") (pin "P$2") (pinfunction "A_P$2") (pintype "bidirectional"))
      (node (ref "UC1") (pin "P$45") (pinfunction "PA24_P$45") (pintype "bidirectional"))
    )
    (net (code "83") (name "PA25") (class "Default")
      (node (ref "U$5") (pin "P$4") (pinfunction "Y_P$4") (pintype "bidirectional"))
      (node (ref "UC1") (pin "P$46") (pinfunction "PA25_P$46") (pintype "bidirectional"))
    )
    (net (code "84") (name "PB01") (class "Default")
      (node (ref "U$6") (pin "29") (pinfunction "P$29_29") (pintype "bidirectional"))
      (node (ref "UC1") (pin "P$62") (pinfunction "PB01_P$62") (pintype "bidirectional"))
    )
    (net (code "85") (name "PB02") (class "Default")
      (node (ref "U$4") (pin "P$1") (pinfunction "OE_P$1") (pintype "bidirectional"))
      (node (ref "UC1") (pin "P$63") (pinfunction "PB02_P$63") (pintype "bidirectional"))
    )
    (net (code "86") (name "PB03") (class "Default")
      (node (ref "U$5") (pin "P$1") (pinfunction "OE_P$1") (pintype "bidirectional"))
      (node (ref "UC1") (pin "P$64") (pinfunction "PB03_P$64") (pintype "bidirectional"))
    )
    (net (code "87") (name "PB15") (class "Default")
      (node (ref "U$2") (pin "6") (pinfunction "POL_6") (pintype "bidirectional"))
      (node (ref "UC1") (pin "P$28") (pinfunction "PB15_P$28") (pintype "bidirectional"))
    )
    (net (code "88") (name "PWR_OUT_SIDE1") (class "Default")
      (node (ref "HEADER1") (pin "P$6") (pinfunction "6_P$6") (pintype "passive"))
    )
    (net (code "89") (name "RESETN") (class "Default")
      (node (ref "SAM-ICE") (pin "15") (pinfunction "15_15") (pintype "passive"))
      (node (ref "UC1") (pin "P$52") (pinfunction "RESETN_P$52") (pintype "input"))
    )
    (net (code "90") (name "SETC") (class "Default")
      (node (ref "C10") (pin "2") (pinfunction "2_2") (pintype "passive"))
      (node (ref "MAG") (pin "12") (pinfunction "SETC_12") (pintype "bidirectional"))
    )
    (net (code "91") (name "SP1_OUT") (class "Default")
      (node (ref "FROM_SIDE1") (pin "P$6") (pinfunction "6_P$6") (pintype "passive"))
    )
    (net (code "92") (name "VIN") (class "Default")
      (node (ref "63001") (pin "P$5") (pinfunction "VIN_P$5") (pintype "input"))
      (node (ref "63001") (pin "P$6") (pinfunction "EN_P$6") (pintype "input"))
      (node (ref "63001") (pin "P$7") (pinfunction "PS/SYNC_P$7") (pintype "input"))
      (node (ref "63001") (pin "P$8") (pinfunction "VINA_P$8") (pintype "input"))
      (node (ref "63002") (pin "P$5") (pinfunction "VIN_P$5") (pintype "input"))
      (node (ref "63002") (pin "P$6") (pinfunction "EN_P$6") (pintype "input"))
      (node (ref "63002") (pin "P$7") (pinfunction "PS/SYNC_P$7") (pintype "input"))
      (node (ref "63002") (pin "P$8") (pinfunction "VINA_P$8") (pintype "input"))
      (node (ref "C12") (pin "1") (pinfunction "1_1") (pintype "passive"))
      (node (ref "C14") (pin "2") (pinfunction "2_2") (pintype "passive"))
      (node (ref "C19") (pin "1") (pinfunction "1_1") (pintype "passive"))
      (node (ref "U$1") (pin "16") (pinfunction "PWM/SYNC_16") (pintype "bidirectional"))
      (node (ref "U$1") (pin "4") (pinfunction "VIN_4") (pintype "bidirectional"))
      (node (ref "U$1") (pin "5") (pinfunction "VIN_5") (pintype "bidirectional"))
    )
    (net (code "93") (name "unconnected-(FROM_FLASH-5-PadP$5)") (class "Default")
      (node (ref "FROM_FLASH") (pin "P$5") (pinfunction "5_P$5") (pintype "passive"))
    )
    (net (code "94") (name "unconnected-(FROM_FLASH-6-PadP$6)") (class "Default")
      (node (ref "FROM_FLASH") (pin "P$6") (pinfunction "6_P$6") (pintype "passive"))
    )
    (net (code "95") (name "unconnected-(FROM_FLASH-7-PadP$7)") (class "Default")
      (node (ref "FROM_FLASH") (pin "P$7") (pinfunction "7_P$7") (pintype "passive"))
    )
    (net (code "96") (name "unconnected-(FROM_SIDE1-1-PadP$1)") (class "Default")
      (node (ref "FROM_SIDE1") (pin "P$1") (pinfunction "1_P$1") (pintype "passive"))
    )
    (net (code "97") (name "unconnected-(HEADER1-1-PadP$1)") (class "Default")
      (node (ref "HEADER1") (pin "P$1") (pinfunction "1_P$1") (pintype "passive"))
    )
    (net (code "98") (name "unconnected-(HEADER7-9-PadP$9)") (class "Default")
      (node (ref "HEADER7") (pin "P$9") (pinfunction "9_P$9") (pintype "passive"))
    )
    (net (code "99") (name "unconnected-(HEADER7-10-PadP$10)") (class "Default")
      (node (ref "HEADER7") (pin "P$10") (pinfunction "10_P$10") (pintype "passive"))
    )
    (net (code "100") (name "unconnected-(HEADER7-11-PadP$11)") (class "Default")
      (node (ref "HEADER7") (pin "P$11") (pinfunction "11_P$11") (pintype "passive"))
    )
    (net (code "101") (name "unconnected-(HEADER7-12-PadP$12)") (class "Default")
      (node (ref "HEADER7") (pin "P$12") (pinfunction "12_P$12") (pintype "passive"))
    )
    (net (code "102") (name "unconnected-(HEADER9-3-PadP$3)") (class "Default")
      (node (ref "HEADER9") (pin "P$3") (pinfunction "3_P$3") (pintype "passive"))
    )
    (net (code "103") (name "unconnected-(HEADER9-4-PadP$4)") (class "Default")
      (node (ref "HEADER9") (pin "P$4") (pinfunction "4_P$4") (pintype "passive"))
    )
    (net (code "104") (name "unconnected-(HEADER9-5-PadP$5)") (class "Default")
      (node (ref "HEADER9") (pin "P$5") (pinfunction "5_P$5") (pintype "passive"))
    )
    (net (code "105") (name "unconnected-(HEADER9-6-PadP$6)") (class "Default")
      (node (ref "HEADER9") (pin "P$6") (pinfunction "6_P$6") (pintype "passive"))
    )
    (net (code "106") (name "unconnected-(HEADER9-7-PadP$7)") (class "Default")
      (node (ref "HEADER9") (pin "P$7") (pinfunction "7_P$7") (pintype "passive"))
    )
    (net (code "107") (name "unconnected-(LED_TEMP_1-NC1-Pad1)") (class "Default")
      (node (ref "LED_TEMP_1") (pin "1") (pinfunction "NC1_1") (pintype "bidirectional"))
    )
    (net (code "108") (name "unconnected-(LED_TEMP_1-NC2-Pad4)") (class "Default")
      (node (ref "LED_TEMP_1") (pin "4") (pinfunction "NC2_4") (pintype "bidirectional"))
    )
    (net (code "109") (name "unconnected-(LED_TEMP_1-NC3-Pad5)") (class "Default")
      (node (ref "LED_TEMP_1") (pin "5") (pinfunction "NC3_5") (pintype "bidirectional"))
    )
    (net (code "110") (name "unconnected-(LED_TEMP_1-NC4-Pad6)") (class "Default")
      (node (ref "LED_TEMP_1") (pin "6") (pinfunction "NC4_6") (pintype "bidirectional"))
    )
    (net (code "111") (name "unconnected-(LED_TEMP_1-NC5-Pad7)") (class "Default")
      (node (ref "LED_TEMP_1") (pin "7") (pinfunction "NC5_7") (pintype "bidirectional"))
    )
    (net (code "112") (name "unconnected-(LED_TEMP_1-NC6-Pad8)") (class "Default")
      (node (ref "LED_TEMP_1") (pin "8") (pinfunction "NC6_8") (pintype "bidirectional"))
    )
    (net (code "113") (name "unconnected-(LED_TEMP_1-V+-Pad2)") (class "Default")
      (node (ref "LED_TEMP_1") (pin "2") (pinfunction "V+_2") (pintype "bidirectional"))
    )
    (net (code "114") (name "unconnected-(LED_TEMP_2-NC1-Pad1)") (class "Default")
      (node (ref "LED_TEMP_2") (pin "1") (pinfunction "NC1_1") (pintype "bidirectional"))
    )
    (net (code "115") (name "unconnected-(LED_TEMP_2-NC2-Pad4)") (class "Default")
      (node (ref "LED_TEMP_2") (pin "4") (pinfunction "NC2_4") (pintype "bidirectional"))
    )
    (net (code "116") (name "unconnected-(LED_TEMP_2-NC3-Pad5)") (class "Default")
      (node (ref "LED_TEMP_2") (pin "5") (pinfunction "NC3_5") (pintype "bidirectional"))
    )
    (net (code "117") (name "unconnected-(LED_TEMP_2-NC4-Pad6)") (class "Default")
      (node (ref "LED_TEMP_2") (pin "6") (pinfunction "NC4_6") (pintype "bidirectional"))
    )
    (net (code "118") (name "unconnected-(LED_TEMP_2-NC5-Pad7)") (class "Default")
      (node (ref "LED_TEMP_2") (pin "7") (pinfunction "NC5_7") (pintype "bidirectional"))
    )
    (net (code "119") (name "unconnected-(LED_TEMP_2-NC6-Pad8)") (class "Default")
      (node (ref "LED_TEMP_2") (pin "8") (pinfunction "NC6_8") (pintype "bidirectional"))
    )
    (net (code "120") (name "unconnected-(MAG-NC-Pad3)") (class "Default")
      (node (ref "MAG") (pin "3") (pinfunction "NC_3") (pintype "bidirectional"))
    )
    (net (code "121") (name "unconnected-(MAG-NC-Pad5)") (class "Default")
      (node (ref "MAG") (pin "5") (pinfunction "NC_5") (pintype "bidirectional"))
    )
    (net (code "122") (name "unconnected-(MAG-NC-Pad6)") (class "Default")
      (node (ref "MAG") (pin "6") (pinfunction "NC_6") (pintype "bidirectional"))
    )
    (net (code "123") (name "unconnected-(MAG-NC-Pad7)") (class "Default")
      (node (ref "MAG") (pin "7") (pinfunction "NC_7") (pintype "bidirectional"))
    )
    (net (code "124") (name "unconnected-(MAG-NC-Pad14)") (class "Default")
      (node (ref "MAG") (pin "14") (pinfunction "NC_14") (pintype "bidirectional"))
    )
    (net (code "125") (name "unconnected-(SAM-ICE-Pad2)") (class "Default")
      (node (ref "SAM-ICE") (pin "2") (pinfunction "2_2") (pintype "passive"))
    )
    (net (code "126") (name "unconnected-(SAM-ICE-Pad3)") (class "Default")
      (node (ref "SAM-ICE") (pin "3") (pinfunction "3_3") (pintype "passive"))
    )
    (net (code "127") (name "unconnected-(SAM-ICE-Pad4)") (class "Default")
      (node (ref "SAM-ICE") (pin "4") (pinfunction "4_4") (pintype "passive"))
    )
    (net (code "128") (name "unconnected-(SAM-ICE-Pad5)") (class "Default")
      (node (ref "SAM-ICE") (pin "5") (pinfunction "5_5") (pintype "passive"))
    )
    (net (code "129") (name "unconnected-(SAM-ICE-Pad6)") (class "Default")
      (node (ref "SAM-ICE") (pin "6") (pinfunction "6_6") (pintype "passive"))
    )
    (net (code "130") (name "unconnected-(SAM-ICE-Pad8)") (class "Default")
      (node (ref "SAM-ICE") (pin "8") (pinfunction "8_8") (pintype "passive"))
    )
    (net (code "131") (name "unconnected-(SAM-ICE-Pad10)") (class "Default")
      (node (ref "SAM-ICE") (pin "10") (pinfunction "10_10") (pintype "passive"))
    )
    (net (code "132") (name "unconnected-(SAM-ICE-Pad11)") (class "Default")
      (node (ref "SAM-ICE") (pin "11") (pinfunction "11_11") (pintype "passive"))
    )
    (net (code "133") (name "unconnected-(SAM-ICE-Pad12)") (class "Default")
      (node (ref "SAM-ICE") (pin "12") (pinfunction "12_12") (pintype "passive"))
    )
    (net (code "134") (name "unconnected-(SAM-ICE-Pad13)") (class "Default")
      (node (ref "SAM-ICE") (pin "13") (pinfunction "13_13") (pintype "passive"))
    )
    (net (code "135") (name "unconnected-(SAM-ICE-Pad14)") (class "Default")
      (node (ref "SAM-ICE") (pin "14") (pinfunction "14_14") (pintype "passive"))
    )
    (net (code "136") (name "unconnected-(SAM-ICE-Pad16)") (class "Default")
      (node (ref "SAM-ICE") (pin "16") (pinfunction "16_16") (pintype "passive"))
    )
    (net (code "137") (name "unconnected-(SAM-ICE-Pad17)") (class "Default")
      (node (ref "SAM-ICE") (pin "17") (pinfunction "17_17") (pintype "passive"))
    )
    (net (code "138") (name "unconnected-(SAM-ICE-Pad18)") (class "Default")
      (node (ref "SAM-ICE") (pin "18") (pinfunction "18_18") (pintype "passive"))
    )
    (net (code "139") (name "unconnected-(SAM-ICE-Pad19)") (class "Default")
      (node (ref "SAM-ICE") (pin "19") (pinfunction "19_19") (pintype "passive"))
    )
    (net (code "140") (name "unconnected-(SAM-ICE-Pad20)") (class "Default")
      (node (ref "SAM-ICE") (pin "20") (pinfunction "20_20") (pintype "passive"))
    )
    (net (code "141") (name "unconnected-(U$1-COMP-Pad1)") (class "Default")
      (node (ref "U$1") (pin "1") (pinfunction "COMP_1") (pintype "bidirectional"))
    )
    (net (code "142") (name "unconnected-(U$1-IOUT-Pad7)") (class "Default")
      (node (ref "U$1") (pin "7") (pinfunction "IOUT_7") (pintype "bidirectional"))
    )
    (net (code "143") (name "unconnected-(U$1-OVP-Pad3)") (class "Default")
      (node (ref "U$1") (pin "3") (pinfunction "OVP_3") (pintype "bidirectional"))
    )
    (net (code "144") (name "unconnected-(U$1-RUN-Pad6)") (class "Default")
      (node (ref "U$1") (pin "6") (pinfunction "RUN_6") (pintype "bidirectional"))
    )
    (net (code "145") (name "unconnected-(U$2-CLR-Pad9)") (class "Default")
      (node (ref "U$2") (pin "9") (pinfunction "CLR_9") (pintype "bidirectional"))
    )
    (net (code "146") (name "unconnected-(U$2-SENSE+-Pad1)") (class "Default")
      (node (ref "U$2") (pin "1") (pinfunction "SENSE+_1") (pintype "bidirectional"))
    )
    (net (code "147") (name "unconnected-(U$2-SENSE--Pad2)") (class "Default")
      (node (ref "U$2") (pin "2") (pinfunction "SENSE-_2") (pintype "bidirectional"))
    )
    (net (code "148") (name "unconnected-(U$6-P$16-Pad16)") (class "Default")
      (node (ref "U$6") (pin "16") (pinfunction "P$16_16") (pintype "bidirectional"))
    )
    (net (code "149") (name "unconnected-(U$6-P$17-Pad17)") (class "Default")
      (node (ref "U$6") (pin "17") (pinfunction "P$17_17") (pintype "bidirectional"))
    )
    (net (code "150") (name "unconnected-(U$6-PadP$6)") (class "Default")
      (node (ref "U$6") (pin "P$6") (pinfunction "P$6_P$6") (pintype "bidirectional"))
    )
    (net (code "151") (name "unconnected-(U$6-PadP$8)") (class "Default")
      (node (ref "U$6") (pin "P$8") (pinfunction "P$8_P$8") (pintype "bidirectional"))
    )
    (net (code "152") (name "unconnected-(U$6-PadP$10)") (class "Default")
      (node (ref "U$6") (pin "P$10") (pinfunction "P$10_P$10") (pintype "bidirectional"))
    )
    (net (code "153") (name "unconnected-(U$6-PadP$11)") (class "Default")
      (node (ref "U$6") (pin "P$11") (pinfunction "P$11_P$11") (pintype "bidirectional"))
    )
    (net (code "154") (name "unconnected-(U$6-PadP$13)") (class "Default")
      (node (ref "U$6") (pin "P$13") (pinfunction "P$13_P$13") (pintype "bidirectional"))
    )
    (net (code "155") (name "unconnected-(U$6-PadP$15)") (class "Default")
      (node (ref "U$6") (pin "P$15") (pinfunction "P$15_P$15") (pintype "bidirectional"))
    )
    (net (code "156") (name "unconnected-(U$7-NC1-Pad1)") (class "Default")
      (node (ref "U$7") (pin "1") (pinfunction "NC1_1") (pintype "bidirectional"))
    )
    (net (code "157") (name "unconnected-(U$7-NC2-Pad4)") (class "Default")
      (node (ref "U$7") (pin "4") (pinfunction "NC2_4") (pintype "bidirectional"))
    )
    (net (code "158") (name "unconnected-(U$7-NC3-Pad5)") (class "Default")
      (node (ref "U$7") (pin "5") (pinfunction "NC3_5") (pintype "bidirectional"))
    )
    (net (code "159") (name "unconnected-(U$7-NC4-Pad6)") (class "Default")
      (node (ref "U$7") (pin "6") (pinfunction "NC4_6") (pintype "bidirectional"))
    )
    (net (code "160") (name "unconnected-(U$7-NC5-Pad7)") (class "Default")
      (node (ref "U$7") (pin "7") (pinfunction "NC5_7") (pintype "bidirectional"))
    )
    (net (code "161") (name "unconnected-(U$7-NC6-Pad8)") (class "Default")
      (node (ref "U$7") (pin "8") (pinfunction "NC6_8") (pintype "bidirectional"))
    )
    (net (code "162") (name "unconnected-(U$8-NC1-Pad1)") (class "Default")
      (node (ref "U$8") (pin "1") (pinfunction "NC1_1") (pintype "bidirectional"))
    )
    (net (code "163") (name "unconnected-(U$8-NC2-Pad4)") (class "Default")
      (node (ref "U$8") (pin "4") (pinfunction "NC2_4") (pintype "bidirectional"))
    )
    (net (code "164") (name "unconnected-(U$8-NC3-Pad5)") (class "Default")
      (node (ref "U$8") (pin "5") (pinfunction "NC3_5") (pintype "bidirectional"))
    )
    (net (code "165") (name "unconnected-(U$8-NC4-Pad6)") (class "Default")
      (node (ref "U$8") (pin "6") (pinfunction "NC4_6") (pintype "bidirectional"))
    )
    (net (code "166") (name "unconnected-(U$8-NC5-Pad7)") (class "Default")
      (node (ref "U$8") (pin "7") (pinfunction "NC5_7") (pintype "bidirectional"))
    )
    (net (code "167") (name "unconnected-(U$8-NC6-Pad8)") (class "Default")
      (node (ref "U$8") (pin "8") (pinfunction "NC6_8") (pintype "bidirectional"))
    )
    (net (code "168") (name "unconnected-(U$9-NC1-Pad1)") (class "Default")
      (node (ref "U$9") (pin "1") (pinfunction "NC1_1") (pintype "bidirectional"))
    )
    (net (code "169") (name "unconnected-(U$9-NC2-Pad4)") (class "Default")
      (node (ref "U$9") (pin "4") (pinfunction "NC2_4") (pintype "bidirectional"))
    )
    (net (code "170") (name "unconnected-(U$9-NC3-Pad5)") (class "Default")
      (node (ref "U$9") (pin "5") (pinfunction "NC3_5") (pintype "bidirectional"))
    )
    (net (code "171") (name "unconnected-(U$9-NC4-Pad6)") (class "Default")
      (node (ref "U$9") (pin "6") (pinfunction "NC4_6") (pintype "bidirectional"))
    )
    (net (code "172") (name "unconnected-(U$9-NC5-Pad7)") (class "Default")
      (node (ref "U$9") (pin "7") (pinfunction "NC5_7") (pintype "bidirectional"))
    )
    (net (code "173") (name "unconnected-(U$9-NC6-Pad8)") (class "Default")
      (node (ref "U$9") (pin "8") (pinfunction "NC6_8") (pintype "bidirectional"))
    )
    (net (code "174") (name "unconnected-(U$10-NC1-Pad1)") (class "Default")
      (node (ref "U$10") (pin "1") (pinfunction "NC1_1") (pintype "bidirectional"))
    )
    (net (code "175") (name "unconnected-(U$10-NC2-Pad4)") (class "Default")
      (node (ref "U$10") (pin "4") (pinfunction "NC2_4") (pintype "bidirectional"))
    )
    (net (code "176") (name "unconnected-(U$10-NC3-Pad5)") (class "Default")
      (node (ref "U$10") (pin "5") (pinfunction "NC3_5") (pintype "bidirectional"))
    )
    (net (code "177") (name "unconnected-(U$10-NC4-Pad6)") (class "Default")
      (node (ref "U$10") (pin "6") (pinfunction "NC4_6") (pintype "bidirectional"))
    )
    (net (code "178") (name "unconnected-(U$10-NC5-Pad7)") (class "Default")
      (node (ref "U$10") (pin "7") (pinfunction "NC5_7") (pintype "bidirectional"))
    )
    (net (code "179") (name "unconnected-(U$10-NC6-Pad8)") (class "Default")
      (node (ref "U$10") (pin "8") (pinfunction "NC6_8") (pintype "bidirectional"))
    )
    (net (code "180") (name "unconnected-(UC1-PA02-PadP$3)") (class "Default")
      (node (ref "UC1") (pin "P$3") (pinfunction "PA02_P$3") (pintype "bidirectional"))
    )
    (net (code "181") (name "unconnected-(UC1-PA03-PadP$4)") (class "Default")
      (node (ref "UC1") (pin "P$4") (pinfunction "PA03_P$4") (pintype "bidirectional"))
    )
    (net (code "182") (name "unconnected-(UC1-PA07-PadP$16)") (class "Default")
      (node (ref "UC1") (pin "P$16") (pinfunction "PA07_P$16") (pintype "bidirectional"))
    )
    (net (code "183") (name "unconnected-(UC1-PA08-PadP$17)") (class "Default")
      (node (ref "UC1") (pin "P$17") (pinfunction "PA08_P$17") (pintype "bidirectional"))
    )
    (net (code "184") (name "unconnected-(UC1-PA09-PadP$18)") (class "Default")
      (node (ref "UC1") (pin "P$18") (pinfunction "PA09_P$18") (pintype "bidirectional"))
    )
    (net (code "185") (name "unconnected-(UC1-PA10-PadP$19)") (class "Default")
      (node (ref "UC1") (pin "P$19") (pinfunction "PA10_P$19") (pintype "bidirectional"))
    )
    (net (code "186") (name "unconnected-(UC1-PA11-PadP$20)") (class "Default")
      (node (ref "UC1") (pin "P$20") (pinfunction "PA11_P$20") (pintype "bidirectional"))
    )
    (net (code "187") (name "unconnected-(UC1-PA15-PadP$32)") (class "Default")
      (node (ref "UC1") (pin "P$32") (pinfunction "PA15_P$32") (pintype "bidirectional"))
    )
    (net (code "188") (name "unconnected-(UC1-PA16-PadP$35)") (class "Default")
      (node (ref "UC1") (pin "P$35") (pinfunction "PA16_P$35") (pintype "bidirectional"))
    )
    (net (code "189") (name "unconnected-(UC1-PA17-PadP$36)") (class "Default")
      (node (ref "UC1") (pin "P$36") (pinfunction "PA17_P$36") (pintype "bidirectional"))
    )
    (net (code "190") (name "unconnected-(UC1-PA27-PadP$51)") (class "Default")
      (node (ref "UC1") (pin "P$51") (pinfunction "PA27_P$51") (pintype "bidirectional"))
    )
    (net (code "191") (name "unconnected-(UC1-PA28-PadP$53)") (class "Default")
      (node (ref "UC1") (pin "P$53") (pinfunction "PA28_P$53") (pintype "bidirectional"))
    )
    (net (code "192") (name "unconnected-(UC1-PB06-PadP$9)") (class "Default")
      (node (ref "UC1") (pin "P$9") (pinfunction "PB06_P$9") (pintype "bidirectional"))
    )
    (net (code "193") (name "unconnected-(UC1-PB07-PadP$10)") (class "Default")
      (node (ref "UC1") (pin "P$10") (pinfunction "PB07_P$10") (pintype "bidirectional"))
    )
    (net (code "194") (name "unconnected-(UC1-PB10-PadP$23)") (class "Default")
      (node (ref "UC1") (pin "P$23") (pinfunction "PB10_P$23") (pintype "bidirectional"))
    )
    (net (code "195") (name "unconnected-(UC1-PB11-PadP$24)") (class "Default")
      (node (ref "UC1") (pin "P$24") (pinfunction "PB11_P$24") (pintype "bidirectional"))
    )
    (net (code "196") (name "unconnected-(UC1-PB12-PadP$25)") (class "Default")
      (node (ref "UC1") (pin "P$25") (pinfunction "PB12_P$25") (pintype "bidirectional"))
    )
    (net (code "197") (name "unconnected-(UC1-PB13-PadP$26)") (class "Default")
      (node (ref "UC1") (pin "P$26") (pinfunction "PB13_P$26") (pintype "bidirectional"))
    )
    (net (code "198") (name "unconnected-(UC1-PB14-PadP$27)") (class "Default")
      (node (ref "UC1") (pin "P$27") (pinfunction "PB14_P$27") (pintype "bidirectional"))
    )
    (net (code "199") (name "unconnected-(UC1-PB22-PadP$49)") (class "Default")
      (node (ref "UC1") (pin "P$49") (pinfunction "PB22_P$49") (pintype "bidirectional"))
    )
    (net (code "200") (name "unconnected-(UC1-PB23-PadP$50)") (class "Default")
      (node (ref "UC1") (pin "P$50") (pinfunction "PB23_P$50") (pintype "bidirectional"))
    )
    (net (code "201") (name "unconnected-(UC1-PB30-PadP$59)") (class "Default")
      (node (ref "UC1") (pin "P$59") (pinfunction "PB30_P$59") (pintype "bidirectional"))
    )
    (net (code "202") (name "unconnected-(UC1-PB31-PadP$60)") (class "Default")
      (node (ref "UC1") (pin "P$60") (pinfunction "PB31_P$60") (pintype "bidirectional"))
    )
  )
)
